# motorcontrol.net
KiCad netlist of a schematic drawn in EAGLE
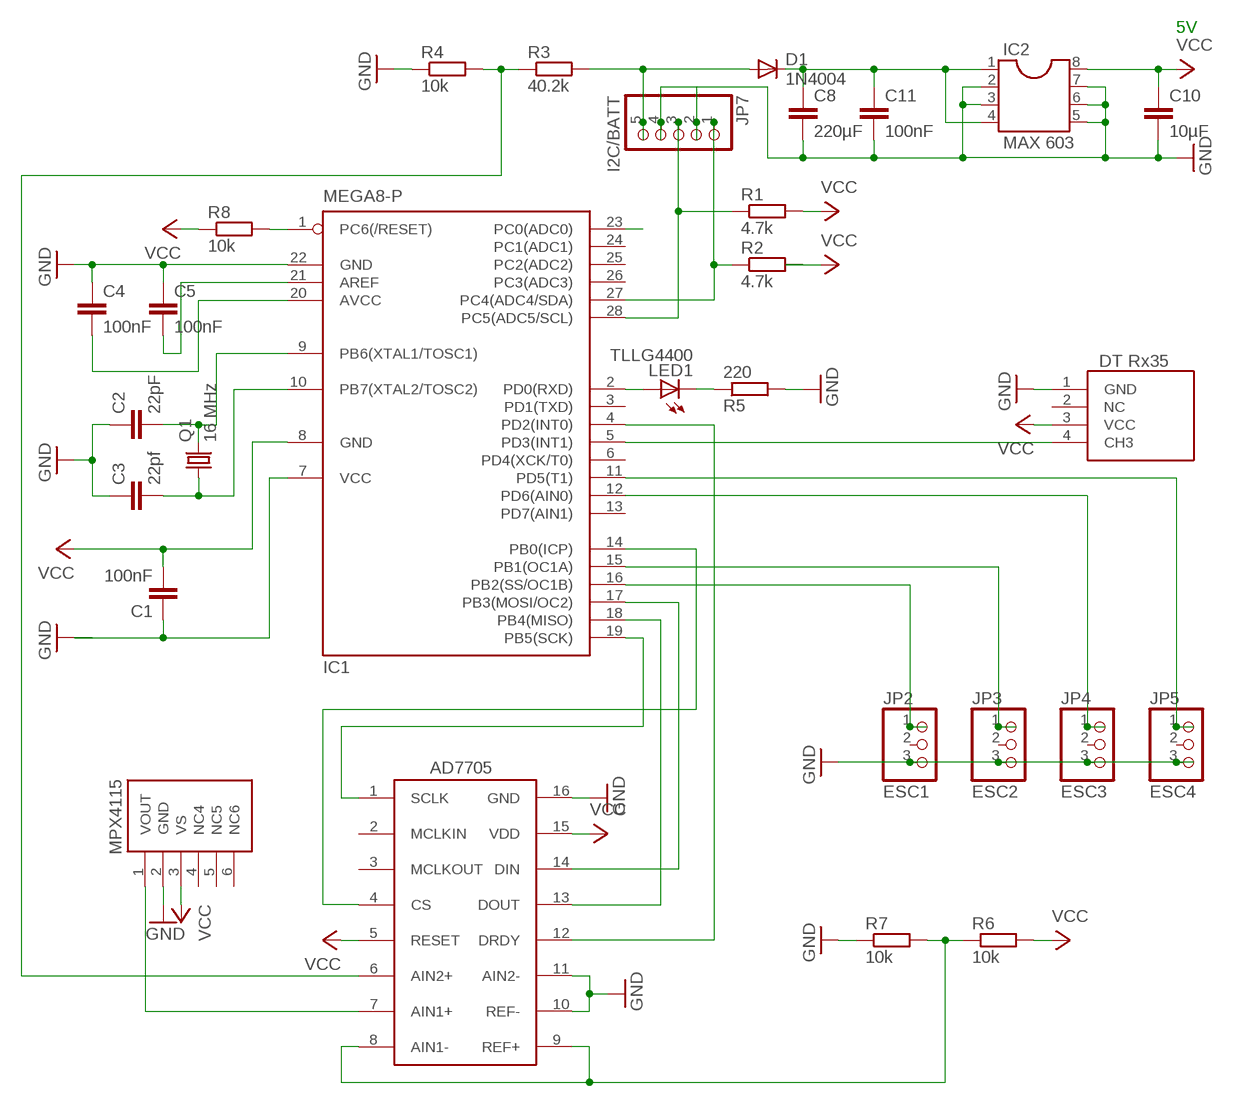
[diagram p0: schematic, sheet 1]

(export (version "E")
  (design (tool "Eeschema 10.0.6"))
  (components
    (comp (ref "C1")
      (value "100nF")
      (footprint "eagle-import:C2.5-2")
      (libsource (lib "eagle-import") (part "C2.5/2"))
    )
    (comp (ref "C2")
      (value "22pF")
      (footprint "eagle-import:C2.5-2")
      (libsource (lib "eagle-import") (part "C2.5/2"))
    )
    (comp (ref "C3")
      (value "22pf")
      (footprint "eagle-import:C2.5-2")
      (libsource (lib "eagle-import") (part "C2.5/2"))
    )
    (comp (ref "C4")
      (value "100nF")
      (footprint "eagle-import:C2.5-2")
      (libsource (lib "eagle-import") (part "C2.5/2"))
    )
    (comp (ref "C5")
      (value "100nF")
      (footprint "eagle-import:C2.5-2")
      (libsource (lib "eagle-import") (part "C2.5/2"))
    )
    (comp (ref "C8")
      (value "220µF")
      (footprint "eagle-import:C2.5-6")
      (libsource (lib "eagle-import") (part "C2.5/6"))
    )
    (comp (ref "C10")
      (value "10µF")
      (footprint "eagle-import:C2.5-5")
      (libsource (lib "eagle-import") (part "C2.5/5"))
    )
    (comp (ref "C11")
      (value "100nF")
      (footprint "eagle-import:C2.5-2")
      (libsource (lib "eagle-import") (part "C2.5/2"))
    )
    (comp (ref "D1")
      (value "1N4004")
      (footprint "eagle-import:DO41-10")
      (libsource (lib "eagle-import") (part "1N4004"))
    )
    (comp (ref "IC1")
      (value "MEGA8-P")
      (footprint "eagle-import:DIL28-3")
      (libsource (lib "eagle-import") (part "MEGA8-P"))
    )
    (comp (ref "IC2")
      (value "MAX 603")
      (footprint "eagle-import:SOCKET-08")
      (libsource (lib "eagle-import") (part "DIL8S"))
    )
    (comp (ref "JP2")
      (value "ESC1")
      (footprint "eagle-import:1X03_90")
      (libsource (lib "eagle-import") (part "PINHD-1X3/90"))
    )
    (comp (ref "JP3")
      (value "ESC2")
      (footprint "eagle-import:1X03_90")
      (libsource (lib "eagle-import") (part "PINHD-1X3/90"))
    )
    (comp (ref "JP4")
      (value "ESC3")
      (footprint "eagle-import:1X03_90")
      (libsource (lib "eagle-import") (part "PINHD-1X3/90"))
    )
    (comp (ref "JP5")
      (value "ESC4")
      (footprint "eagle-import:1X03_90")
      (libsource (lib "eagle-import") (part "PINHD-1X3/90"))
    )
    (comp (ref "JP7")
      (value "I2C/BATT")
      (footprint "eagle-import:1X05")
      (libsource (lib "eagle-import") (part "PINHD-1X5"))
    )
    (comp (ref "LED1")
      (value "TLLG4400")
      (footprint "eagle-import:LED3MM")
      (fields (field (name "MF") "VISHAY SEMICONDUCTOR"))
      (libsource (lib "eagle-import") (part "TLLG4400"))
    )
    (comp (ref "Q1")
      (value "16 MHz")
      (footprint "eagle-import:HC49_S")
      (libsource (lib "eagle-import") (part "CRYSTALHC49S"))
    )
    (comp (ref "R1")
      (value "4.7k")
      (footprint "eagle-import:0207_2V")
      (libsource (lib "eagle-import") (part "R-EU_0207/2V"))
    )
    (comp (ref "R2")
      (value "4.7k")
      (footprint "eagle-import:0207_2V")
      (libsource (lib "eagle-import") (part "R-EU_0207/2V"))
    )
    (comp (ref "R3")
      (value "40.2k")
      (footprint "eagle-import:0207_2V")
      (libsource (lib "eagle-import") (part "R-EU_0207/2V"))
    )
    (comp (ref "R4")
      (value "10k")
      (footprint "eagle-import:0207_2V")
      (libsource (lib "eagle-import") (part "R-EU_0207/2V"))
    )
    (comp (ref "R5")
      (value "220")
      (footprint "eagle-import:0207_10")
      (libsource (lib "eagle-import") (part "R-EU_0207/10"))
    )
    (comp (ref "R6")
      (value "10k")
      (footprint "eagle-import:0207_2V")
      (libsource (lib "eagle-import") (part "R-EU_0207/2V"))
    )
    (comp (ref "R7")
      (value "10k")
      (footprint "eagle-import:0207_2V")
      (libsource (lib "eagle-import") (part "R-EU_0207/2V"))
    )
    (comp (ref "R8")
      (value "10k")
      (footprint "eagle-import:0207_2V")
      (libsource (lib "eagle-import") (part "R-EU_0207/2V"))
    )
    (comp (ref "U$1")
      (value "AD7705")
      (footprint "eagle-import:AD7705BNC")
      (libsource (lib "eagle-import") (part "AD7705"))
    )
    (comp (ref "U$2")
      (value "DTRX35")
      (footprint "eagle-import:DTRX35")
      (libsource (lib "eagle-import") (part "DTRX35"))
    )
    (comp (ref "U$3")
      (value "MPX4115")
      (footprint "eagle-import:MPX4115")
      (libsource (lib "eagle-import") (part "MPX4115"))
    )
  )
  (nets
    (net (code "1") (name "GND") (class "Default")
      (node (ref "C1") (pin "1") (pinfunction "1_1") (pintype "passive"))
      (node (ref "C10") (pin "2") (pinfunction "2_2") (pintype "passive"))
      (node (ref "C11") (pin "2") (pinfunction "2_2") (pintype "passive"))
      (node (ref "C2") (pin "1") (pinfunction "1_1") (pintype "passive"))
      (node (ref "C3") (pin "1") (pinfunction "1_1") (pintype "passive"))
      (node (ref "C4") (pin "1") (pinfunction "1_1") (pintype "passive"))
      (node (ref "C5") (pin "1") (pinfunction "1_1") (pintype "passive"))
      (node (ref "C8") (pin "2") (pinfunction "2_2") (pintype "passive"))
      (node (ref "IC1") (pin "22") (pinfunction "GND_22") (pintype "power_in"))
      (node (ref "IC1") (pin "7") (pinfunction "VCC_7") (pintype "power_in"))
      (node (ref "IC2") (pin "2") (pinfunction "2_2") (pintype "passive"))
      (node (ref "IC2") (pin "3") (pinfunction "3_3") (pintype "passive"))
      (node (ref "IC2") (pin "5") (pinfunction "5_5") (pintype "passive"))
      (node (ref "IC2") (pin "6") (pinfunction "6_6") (pintype "passive"))
      (node (ref "IC2") (pin "7") (pinfunction "7_7") (pintype "passive"))
      (node (ref "JP2") (pin "3") (pinfunction "3_3") (pintype "passive"))
      (node (ref "JP3") (pin "3") (pinfunction "3_3") (pintype "passive"))
      (node (ref "JP4") (pin "3") (pinfunction "3_3") (pintype "passive"))
      (node (ref "JP5") (pin "3") (pinfunction "3_3") (pintype "passive"))
      (node (ref "JP7") (pin "2") (pinfunction "2_2") (pintype "passive"))
      (node (ref "JP7") (pin "4") (pinfunction "4_4") (pintype "passive"))
      (node (ref "R4") (pin "1") (pinfunction "1_1") (pintype "passive"))
      (node (ref "R5") (pin "2") (pinfunction "2_2") (pintype "passive"))
      (node (ref "R7") (pin "1") (pinfunction "1_1") (pintype "passive"))
      (node (ref "U$1") (pin "10") (pinfunction "REF-_10") (pintype "input"))
      (node (ref "U$1") (pin "11") (pinfunction "AIN2-_11") (pintype "input"))
      (node (ref "U$1") (pin "16") (pinfunction "GND_16") (pintype "input"))
      (node (ref "U$2") (pin "1") (pinfunction "GND_1") (pintype "input"))
      (node (ref "U$3") (pin "2") (pinfunction "GND_2") (pintype "input"))
    )
    (net (code "2") (name "Net-(C11-Pad1)") (class "Default")
      (node (ref "C11") (pin "1") (pinfunction "1_1") (pintype "passive"))
      (node (ref "C8") (pin "1") (pinfunction "1_1") (pintype "passive"))
      (node (ref "D1") (pin "C") (pinfunction "C_C") (pintype "passive"))
      (node (ref "IC2") (pin "1") (pinfunction "1_1") (pintype "passive"))
      (node (ref "IC2") (pin "4") (pinfunction "4_4") (pintype "passive"))
    )
    (net (code "3") (name "Net-(D1-PadA)") (class "Default")
      (node (ref "D1") (pin "A") (pinfunction "A_A") (pintype "passive"))
      (node (ref "JP7") (pin "5") (pinfunction "5_5") (pintype "passive"))
      (node (ref "R3") (pin "2") (pinfunction "2_2") (pintype "passive"))
    )
    (net (code "4") (name "Net-(IC1-AREF)") (class "Default")
      (node (ref "C5") (pin "2") (pinfunction "2_2") (pintype "passive"))
      (node (ref "IC1") (pin "21") (pinfunction "AREF_21") (pintype "passive"))
    )
    (net (code "5") (name "Net-(IC1-AVCC)") (class "Default")
      (node (ref "C4") (pin "2") (pinfunction "2_2") (pintype "passive"))
      (node (ref "IC1") (pin "20") (pinfunction "AVCC_20") (pintype "power_in"))
    )
    (net (code "6") (name "Net-(IC1-PB0(ICP))") (class "Default")
      (node (ref "IC1") (pin "14") (pinfunction "PB0(ICP)_14") (pintype "bidirectional"))
      (node (ref "U$1") (pin "4") (pinfunction "CS_4") (pintype "input"))
    )
    (net (code "7") (name "Net-(IC1-PB1(OC1A))") (class "Default")
      (node (ref "IC1") (pin "15") (pinfunction "PB1(OC1A)_15") (pintype "bidirectional"))
      (node (ref "JP3") (pin "1") (pinfunction "1_1") (pintype "passive"))
    )
    (net (code "8") (name "Net-(IC1-PB2(SS{slash}OC1B))") (class "Default")
      (node (ref "IC1") (pin "16") (pinfunction "PB2(SS/OC1B)_16") (pintype "bidirectional"))
      (node (ref "JP2") (pin "1") (pinfunction "1_1") (pintype "passive"))
    )
    (net (code "9") (name "Net-(IC1-PB3(MOSI{slash}OC2))") (class "Default")
      (node (ref "IC1") (pin "17") (pinfunction "PB3(MOSI/OC2)_17") (pintype "bidirectional"))
      (node (ref "U$1") (pin "14") (pinfunction "DIN_14") (pintype "bidirectional"))
    )
    (net (code "10") (name "Net-(IC1-PB4(MISO))") (class "Default")
      (node (ref "IC1") (pin "18") (pinfunction "PB4(MISO)_18") (pintype "bidirectional"))
      (node (ref "U$1") (pin "13") (pinfunction "DOUT_13") (pintype "bidirectional"))
    )
    (net (code "11") (name "Net-(IC1-PB5(SCK))") (class "Default")
      (node (ref "IC1") (pin "19") (pinfunction "PB5(SCK)_19") (pintype "bidirectional"))
      (node (ref "U$1") (pin "1") (pinfunction "SCLK_1") (pintype "bidirectional"))
    )
    (net (code "12") (name "Net-(IC1-PB6(XTAL1{slash}TOSC1))") (class "Default")
      (node (ref "C2") (pin "2") (pinfunction "2_2") (pintype "passive"))
      (node (ref "IC1") (pin "9") (pinfunction "PB6(XTAL1/TOSC1)_9") (pintype "bidirectional"))
      (node (ref "Q1") (pin "2") (pinfunction "2_2") (pintype "passive"))
    )
    (net (code "13") (name "Net-(IC1-PB7(XTAL2{slash}TOSC2))") (class "Default")
      (node (ref "C3") (pin "2") (pinfunction "2_2") (pintype "passive"))
      (node (ref "IC1") (pin "10") (pinfunction "PB7(XTAL2/TOSC2)_10") (pintype "bidirectional"))
      (node (ref "Q1") (pin "1") (pinfunction "1_1") (pintype "passive"))
    )
    (net (code "14") (name "Net-(IC1-PC4(ADC4{slash}SDA))") (class "Default")
      (node (ref "IC1") (pin "27") (pinfunction "PC4(ADC4/SDA)_27") (pintype "bidirectional"))
      (node (ref "JP7") (pin "1") (pinfunction "1_1") (pintype "passive"))
      (node (ref "R2") (pin "1") (pinfunction "1_1") (pintype "passive"))
    )
    (net (code "15") (name "Net-(IC1-PC5(ADC5{slash}SCL))") (class "Default")
      (node (ref "IC1") (pin "28") (pinfunction "PC5(ADC5/SCL)_28") (pintype "bidirectional"))
      (node (ref "JP7") (pin "3") (pinfunction "3_3") (pintype "passive"))
      (node (ref "R1") (pin "1") (pinfunction "1_1") (pintype "passive"))
    )
    (net (code "16") (name "Net-(IC1-PC6({slash}RESET))") (class "Default")
      (node (ref "IC1") (pin "1") (pinfunction "PC6(/RESET)_1") (pintype "bidirectional"))
      (node (ref "R8") (pin "2") (pinfunction "2_2") (pintype "passive"))
    )
    (net (code "17") (name "Net-(IC1-PD0(RXD))") (class "Default")
      (node (ref "IC1") (pin "2") (pinfunction "PD0(RXD)_2") (pintype "bidirectional"))
      (node (ref "LED1") (pin "A") (pinfunction "A_A") (pintype "passive"))
    )
    (net (code "18") (name "Net-(IC1-PD2(INT0))") (class "Default")
      (node (ref "IC1") (pin "4") (pinfunction "PD2(INT0)_4") (pintype "bidirectional"))
      (node (ref "U$1") (pin "12") (pinfunction "DRDY_12") (pintype "bidirectional"))
    )
    (net (code "19") (name "Net-(IC1-PD3(INT1))") (class "Default")
      (node (ref "IC1") (pin "5") (pinfunction "PD3(INT1)_5") (pintype "bidirectional"))
      (node (ref "U$2") (pin "4") (pinfunction "CH3_4") (pintype "output"))
    )
    (net (code "20") (name "Net-(IC1-PD5(T1))") (class "Default")
      (node (ref "IC1") (pin "11") (pinfunction "PD5(T1)_11") (pintype "bidirectional"))
      (node (ref "JP5") (pin "1") (pinfunction "1_1") (pintype "passive"))
    )
    (net (code "21") (name "Net-(IC1-PD6(AIN0))") (class "Default")
      (node (ref "IC1") (pin "12") (pinfunction "PD6(AIN0)_12") (pintype "bidirectional"))
      (node (ref "JP4") (pin "1") (pinfunction "1_1") (pintype "passive"))
    )
    (net (code "22") (name "Net-(LED1-C)") (class "Default")
      (node (ref "LED1") (pin "K") (pinfunction "C_K") (pintype "passive"))
      (node (ref "R5") (pin "1") (pinfunction "1_1") (pintype "passive"))
    )
    (net (code "23") (name "Net-(U$1-AIN1+)") (class "Default")
      (node (ref "U$1") (pin "7") (pinfunction "AIN1+_7") (pintype "input"))
      (node (ref "U$3") (pin "1") (pinfunction "VOUT_1") (pintype "output"))
    )
    (net (code "24") (name "Net-(U$1-AIN1-)") (class "Default")
      (node (ref "R6") (pin "1") (pinfunction "1_1") (pintype "passive"))
      (node (ref "R7") (pin "2") (pinfunction "2_2") (pintype "passive"))
      (node (ref "U$1") (pin "8") (pinfunction "AIN1-_8") (pintype "input"))
      (node (ref "U$1") (pin "9") (pinfunction "REF+_9") (pintype "input"))
    )
    (net (code "25") (name "Net-(U$1-AIN2+)") (class "Default")
      (node (ref "R3") (pin "1") (pinfunction "1_1") (pintype "passive"))
      (node (ref "R4") (pin "2") (pinfunction "2_2") (pintype "passive"))
      (node (ref "U$1") (pin "6") (pinfunction "AIN2+_6") (pintype "input"))
    )
    (net (code "26") (name "VCC") (class "Default")
      (node (ref "C1") (pin "2") (pinfunction "2_2") (pintype "passive"))
      (node (ref "C10") (pin "1") (pinfunction "1_1") (pintype "passive"))
      (node (ref "IC1") (pin "8") (pinfunction "GND_8") (pintype "power_in"))
      (node (ref "IC2") (pin "8") (pinfunction "8_8") (pintype "passive"))
      (node (ref "R1") (pin "2") (pinfunction "2_2") (pintype "passive"))
      (node (ref "R2") (pin "2") (pinfunction "2_2") (pintype "passive"))
      (node (ref "R6") (pin "2") (pinfunction "2_2") (pintype "passive"))
      (node (ref "R8") (pin "1") (pinfunction "1_1") (pintype "passive"))
      (node (ref "U$1") (pin "15") (pinfunction "VDD_15") (pintype "power_in"))
      (node (ref "U$1") (pin "5") (pinfunction "RESET_5") (pintype "input"))
      (node (ref "U$2") (pin "3") (pinfunction "VCC_3") (pintype "power_in"))
      (node (ref "U$3") (pin "3") (pinfunction "VS_3") (pintype "power_in"))
    )
    (net (code "27") (name "unconnected-(IC1-PC0(ADC0)-Pad23)") (class "Default")
      (node (ref "IC1") (pin "23") (pinfunction "PC0(ADC0)_23") (pintype "bidirectional"))
    )
    (net (code "28") (name "unconnected-(IC1-PC1(ADC1)-Pad24)") (class "Default")
      (node (ref "IC1") (pin "24") (pinfunction "PC1(ADC1)_24") (pintype "bidirectional"))
    )
    (net (code "29") (name "unconnected-(IC1-PC2(ADC2)-Pad25)") (class "Default")
      (node (ref "IC1") (pin "25") (pinfunction "PC2(ADC2)_25") (pintype "bidirectional"))
    )
    (net (code "30") (name "unconnected-(IC1-PC3(ADC3)-Pad26)") (class "Default")
      (node (ref "IC1") (pin "26") (pinfunction "PC3(ADC3)_26") (pintype "bidirectional"))
    )
    (net (code "31") (name "unconnected-(IC1-PD1(TXD)-Pad3)") (class "Default")
      (node (ref "IC1") (pin "3") (pinfunction "PD1(TXD)_3") (pintype "bidirectional"))
    )
    (net (code "32") (name "unconnected-(IC1-PD4(XCK{slash}T0)-Pad6)") (class "Default")
      (node (ref "IC1") (pin "6") (pinfunction "PD4(XCK/T0)_6") (pintype "bidirectional"))
    )
    (net (code "33") (name "unconnected-(IC1-PD7(AIN1)-Pad13)") (class "Default")
      (node (ref "IC1") (pin "13") (pinfunction "PD7(AIN1)_13") (pintype "bidirectional"))
    )
    (net (code "34") (name "unconnected-(JP2-Pad2)") (class "Default")
      (node (ref "JP2") (pin "2") (pinfunction "2_2") (pintype "passive"))
    )
    (net (code "35") (name "unconnected-(JP3-Pad2)") (class "Default")
      (node (ref "JP3") (pin "2") (pinfunction "2_2") (pintype "passive"))
    )
    (net (code "36") (name "unconnected-(JP4-Pad2)") (class "Default")
      (node (ref "JP4") (pin "2") (pinfunction "2_2") (pintype "passive"))
    )
    (net (code "37") (name "unconnected-(JP5-Pad2)") (class "Default")
      (node (ref "JP5") (pin "2") (pinfunction "2_2") (pintype "passive"))
    )
    (net (code "38") (name "unconnected-(U$1-MCLKIN-Pad2)") (class "Default")
      (node (ref "U$1") (pin "2") (pinfunction "MCLKIN_2") (pintype "input"))
    )
    (net (code "39") (name "unconnected-(U$1-MCLKOUT-Pad3)") (class "Default")
      (node (ref "U$1") (pin "3") (pinfunction "MCLKOUT_3") (pintype "output"))
    )
    (net (code "40") (name "unconnected-(U$2-NC-Pad2)") (class "Default")
      (node (ref "U$2") (pin "2") (pinfunction "NC_2") (pintype "no_connect"))
    )
    (net (code "41") (name "unconnected-(U$3-NC4-Pad4)") (class "Default")
      (node (ref "U$3") (pin "4") (pinfunction "NC4_4") (pintype "no_connect"))
    )
    (net (code "42") (name "unconnected-(U$3-NC5-Pad5)") (class "Default")
      (node (ref "U$3") (pin "5") (pinfunction "NC5_5") (pintype "no_connect"))
    )
    (net (code "43") (name "unconnected-(U$3-NC6-Pad6)") (class "Default")
      (node (ref "U$3") (pin "6") (pinfunction "NC6_6") (pintype "no_connect"))
    )
  )
)
